# ftdi_adapter.net
KiCad netlist of a schematic drawn in EAGLE
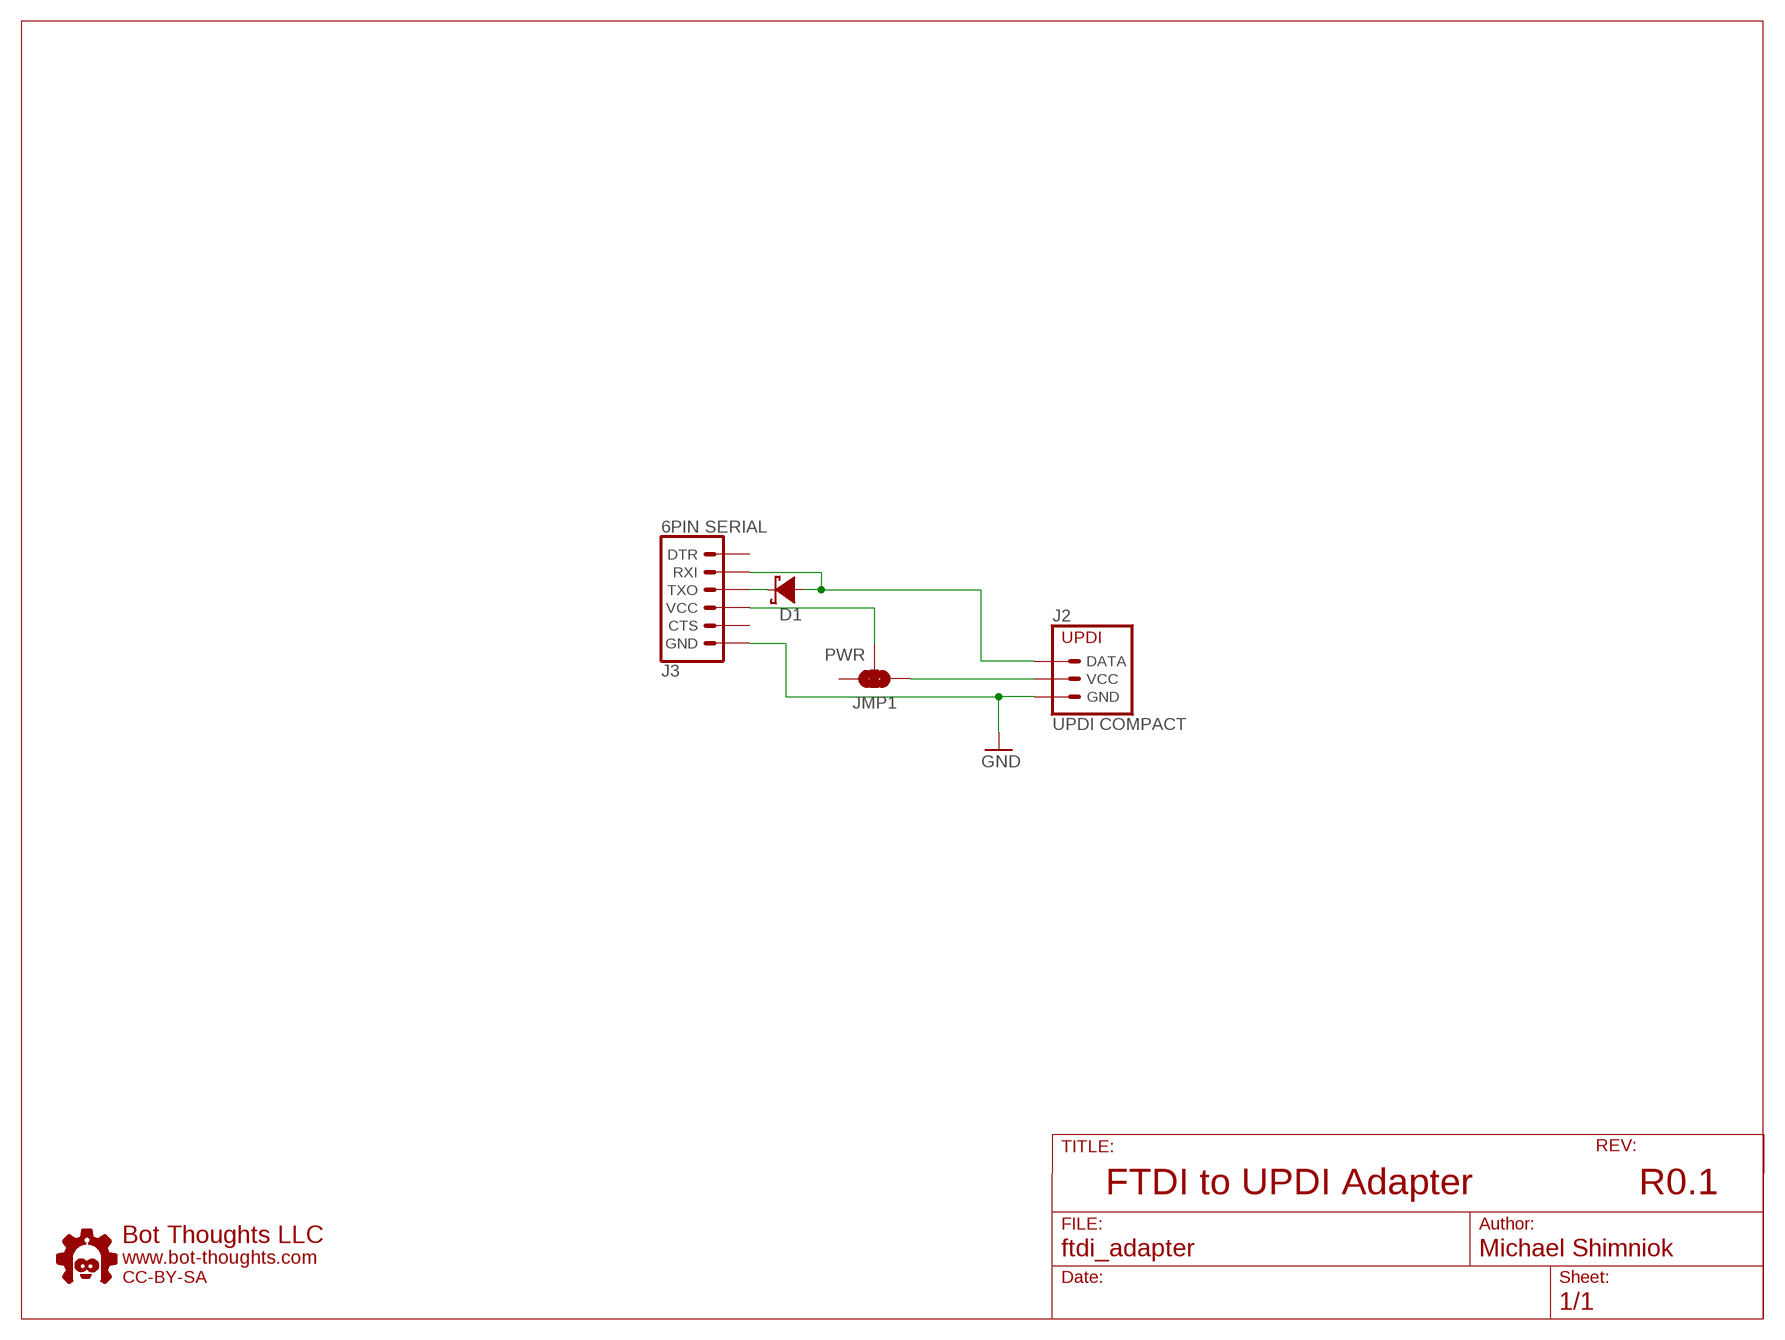
[diagram p0: schematic, sheet 1]

(export (version "E")
  (design (tool "Eeschema 10.0.6"))
  (components
    (comp (ref "D1")
      (value "DIODE-SCHOTTKYSOD-323ORIG")
      (footprint "eagle-import:SOD-323ORIG")
      (libsource (lib "eagle-import") (part "DIODE-SCHOTTKYSOD-323ORIG"))
    )
    (comp (ref "J2")
      (value "UPDI COMPACT")
      (footprint "eagle-import:UPDI_1X3")
      (libsource (lib "eagle-import") (part "UPDI_COMPACT"))
    )
    (comp (ref "J3")
      (value "6PIN SERIAL")
      (footprint "eagle-import:6PIN_TARGET")
      (libsource (lib "eagle-import") (part "6PIN_TARGET_LEFT"))
    )
    (comp (ref "JMP1")
      (value "PWR")
      (footprint "eagle-import:JUMPER-2W-PIN-0.1IN")
      (libsource (lib "eagle-import") (part "JUMPER-2-WAY-PTH-0.1IN"))
    )
    (comp (ref "U$1")
      (value "BTLOGO-LOGO-SM")
      (footprint "eagle-import:BTLOGOS")
      (libsource (lib "eagle-import") (part "BTLOGO-LOGO-SM"))
    )
  )
  (nets
    (net (code "1") (name "GND") (class "Default")
      (node (ref "J2") (pin "2") (pinfunction "GND_2") (pintype "power_in"))
      (node (ref "J3") (pin "6") (pinfunction "GND_6") (pintype "passive"))
    )
    (net (code "2") (name "Net-(J2-DATA)") (class "Default")
      (node (ref "D1") (pin "A") (pinfunction "A_A") (pintype "passive"))
      (node (ref "J2") (pin "3") (pinfunction "DATA_3") (pintype "bidirectional"))
      (node (ref "J3") (pin "2") (pinfunction "RXI_2") (pintype "passive"))
    )
    (net (code "3") (name "Net-(J2-VCC)") (class "Default")
      (node (ref "J2") (pin "1") (pinfunction "VCC_1") (pintype "power_in"))
      (node (ref "JMP1") (pin "1") (pinfunction "1_1") (pintype "passive"))
    )
    (net (code "4") (name "Net-(J3-TXO)") (class "Default")
      (node (ref "D1") (pin "C") (pinfunction "C_C") (pintype "passive"))
      (node (ref "J3") (pin "3") (pinfunction "TXO_3") (pintype "passive"))
    )
    (net (code "5") (name "Net-(J3-VCC)") (class "Default")
      (node (ref "J3") (pin "4") (pinfunction "VCC_4") (pintype "passive"))
      (node (ref "JMP1") (pin "2") (pinfunction "2_2") (pintype "passive"))
    )
    (net (code "6") (name "unconnected-(J3-CTS-Pad5)") (class "Default")
      (node (ref "J3") (pin "5") (pinfunction "CTS_5") (pintype "passive"))
    )
    (net (code "7") (name "unconnected-(J3-DTR-Pad1)") (class "Default")
      (node (ref "J3") (pin "1") (pinfunction "DTR_1") (pintype "passive"))
    )
    (net (code "8") (name "unconnected-(JMP1-Pad3)") (class "Default")
      (node (ref "JMP1") (pin "3") (pinfunction "3_3") (pintype "passive"))
    )
  )
)
